# LCD.net
KiCad netlist of a schematic drawn in Altium Designer
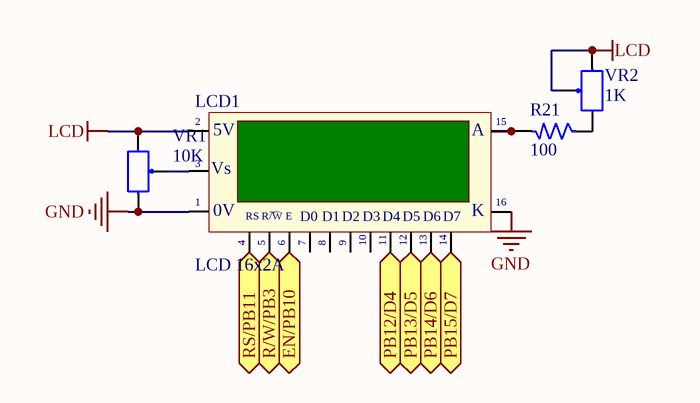
[diagram p0: LCD.SchDoc]

(export (version "E")
  (design (tool "Eeschema 10.0.6"))
  (components
    (comp (ref "LCD1")
      (value "LCD 16x2A")
      (footprint "LCD16X2")
      (description "LCD dipslay 16 char, 2 line")
      (libsource (lib "minhLIB") (part "LCD16x2A"))
    )
    (comp (ref "R21")
      (value "100")
      (footprint "SM-1206")
      (description "Resistor 1/4W")
      (libsource (lib "syhaunguyen") (part "R"))
    )
    (comp (ref "VR1")
      (value "10K")
      (footprint "VR")
      (description "Var Resistor")
      (libsource (lib "syhaunguyen") (part "VR"))
    )
    (comp (ref "VR2")
      (value "1K")
      (footprint "VR")
      (description "Var Resistor")
      (libsource (lib "syhaunguyen") (part "VR"))
    )
  )
  (nets
    (net (code "1") (name "/EN{slash}PB10") (class "Default")
      (node (ref "LCD1") (pin "6") (pinfunction "~{EN}_6") (pintype "passive"))
    )
    (net (code "2") (name "/PB12{slash}D4") (class "Default")
      (node (ref "LCD1") (pin "11") (pinfunction "D4_11") (pintype "passive"))
    )
    (net (code "3") (name "/PB13{slash}D5") (class "Default")
      (node (ref "LCD1") (pin "12") (pinfunction "D5_12") (pintype "passive"))
    )
    (net (code "4") (name "/PB14{slash}D6") (class "Default")
      (node (ref "LCD1") (pin "13") (pinfunction "D6_13") (pintype "passive"))
    )
    (net (code "5") (name "/PB15{slash}D7") (class "Default")
      (node (ref "LCD1") (pin "14") (pinfunction "D7_14") (pintype "passive"))
    )
    (net (code "6") (name "/RS{slash}PB11") (class "Default")
      (node (ref "LCD1") (pin "4") (pinfunction "RS_4") (pintype "passive"))
    )
    (net (code "7") (name "/R{slash}W{slash}PB3") (class "Default")
      (node (ref "LCD1") (pin "5") (pinfunction "R/~{W}_5") (pintype "passive"))
    )
    (net (code "8") (name "GND") (class "Default")
      (node (ref "LCD1") (pin "1") (pinfunction "GND_1") (pintype "passive"))
      (node (ref "LCD1") (pin "16") (pinfunction "K_16") (pintype "passive"))
      (node (ref "VR1") (pin "3") (pinfunction "3_3") (pintype "passive"))
    )
    (net (code "9") (name "LCD") (class "Default")
      (node (ref "LCD1") (pin "2") (pinfunction "VDD_2") (pintype "passive"))
      (node (ref "VR1") (pin "1") (pinfunction "1_1") (pintype "passive"))
      (node (ref "VR2") (pin "2") (pinfunction "2_2") (pintype "passive"))
      (node (ref "VR2") (pin "3") (pinfunction "3_3") (pintype "passive"))
    )
    (net (code "10") (name "Net-(LCD1-A)") (class "Default")
      (node (ref "LCD1") (pin "15") (pinfunction "A_15") (pintype "passive"))
      (node (ref "R21") (pin "2") (pinfunction "2_2") (pintype "passive"))
    )
    (net (code "11") (name "Net-(LCD1-VEE)") (class "Default")
      (node (ref "LCD1") (pin "3") (pinfunction "VEE_3") (pintype "passive"))
      (node (ref "VR1") (pin "2") (pinfunction "2_2") (pintype "passive"))
    )
    (net (code "12") (name "Net-(R21-Pad1)") (class "Default")
      (node (ref "R21") (pin "1") (pinfunction "1_1") (pintype "passive"))
      (node (ref "VR2") (pin "1") (pinfunction "1_1") (pintype "passive"))
    )
    (net (code "13") (name "unconnected-(LCD1-D0-Pad7)") (class "Default")
      (node (ref "LCD1") (pin "7") (pinfunction "D0_7") (pintype "passive"))
    )
    (net (code "14") (name "unconnected-(LCD1-D1-Pad8)") (class "Default")
      (node (ref "LCD1") (pin "8") (pinfunction "D1_8") (pintype "passive"))
    )
    (net (code "15") (name "unconnected-(LCD1-D2-Pad9)") (class "Default")
      (node (ref "LCD1") (pin "9") (pinfunction "D2_9") (pintype "passive"))
    )
    (net (code "16") (name "unconnected-(LCD1-D3-Pad10)") (class "Default")
      (node (ref "LCD1") (pin "10") (pinfunction "D3_10") (pintype "passive"))
    )
  )
)
